# baseboard.net
KiCad netlist of a schematic drawn in EAGLE
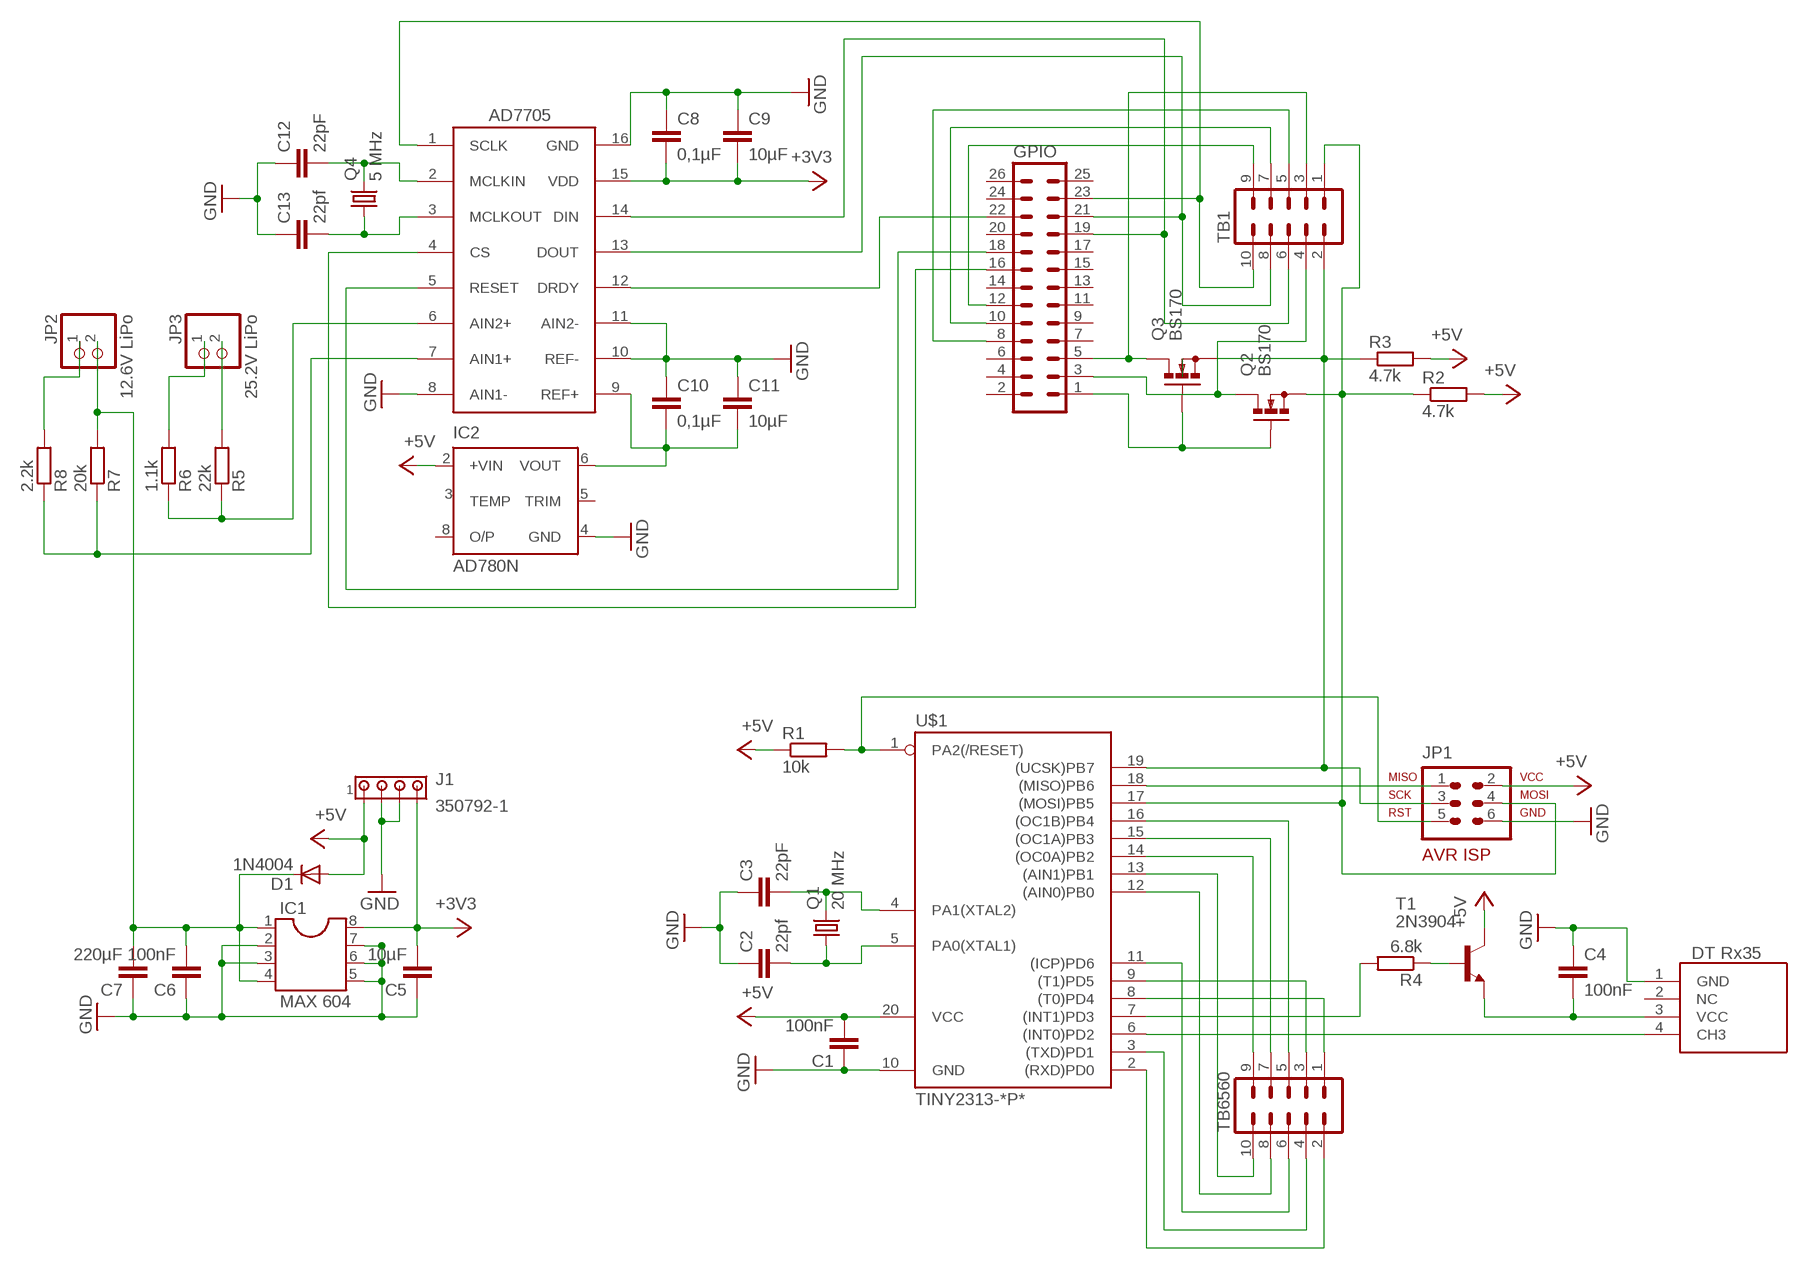
[diagram p0: schematic, sheet 1]

(export (version "E")
  (design (tool "Eeschema 10.0.6"))
  (components
    (comp (ref "C1")
      (value "100nF")
      (footprint "eagle-import:C2.5-2")
      (libsource (lib "eagle-import") (part "C2.5/2"))
    )
    (comp (ref "C2")
      (value "22pf")
      (footprint "eagle-import:C2.5-2")
      (libsource (lib "eagle-import") (part "C2.5/2"))
    )
    (comp (ref "C3")
      (value "22pF")
      (footprint "eagle-import:C2.5-2")
      (libsource (lib "eagle-import") (part "C2.5/2"))
    )
    (comp (ref "C4")
      (value "100nF")
      (footprint "eagle-import:C2.5-2")
      (libsource (lib "eagle-import") (part "C2.5/2"))
    )
    (comp (ref "C5")
      (value "10µF")
      (footprint "eagle-import:C2.5-2")
      (libsource (lib "eagle-import") (part "C2.5/2"))
    )
    (comp (ref "C6")
      (value "100nF")
      (footprint "eagle-import:C2.5-2")
      (libsource (lib "eagle-import") (part "C2.5/2"))
    )
    (comp (ref "C7")
      (value "220µF")
      (footprint "eagle-import:C2.5-2")
      (libsource (lib "eagle-import") (part "C2.5/2"))
    )
    (comp (ref "C8")
      (value "0,1µF")
      (footprint "eagle-import:C2.5-2")
      (libsource (lib "eagle-import") (part "C2.5/2"))
    )
    (comp (ref "C9")
      (value "10µF")
      (footprint "eagle-import:C2.5-2")
      (libsource (lib "eagle-import") (part "C2.5/2"))
    )
    (comp (ref "C10")
      (value "0,1µF")
      (footprint "eagle-import:C2.5-2")
      (libsource (lib "eagle-import") (part "C2.5/2"))
    )
    (comp (ref "C11")
      (value "10µF")
      (footprint "eagle-import:C2.5-2")
      (libsource (lib "eagle-import") (part "C2.5/2"))
    )
    (comp (ref "C12")
      (value "22pF")
      (footprint "eagle-import:C2.5-2")
      (libsource (lib "eagle-import") (part "C2.5/2"))
    )
    (comp (ref "C13")
      (value "22pf")
      (footprint "eagle-import:C2.5-2")
      (libsource (lib "eagle-import") (part "C2.5/2"))
    )
    (comp (ref "D1")
      (value "1N4004")
      (footprint "eagle-import:DO41-10")
      (libsource (lib "eagle-import") (part "1N4004"))
    )
    (comp (ref "GPIO")
      (value "ML26")
      (footprint "eagle-import:ML26")
      (libsource (lib "eagle-import") (part "ML26"))
    )
    (comp (ref "IC1")
      (value "MAX 604")
      (footprint "eagle-import:DIL08")
      (libsource (lib "eagle-import") (part "DIL8"))
    )
    (comp (ref "IC2")
      (value "AD780N")
      (footprint "eagle-import:DIL08")
      (fields (field (name "MF") "ALTERA CORPORATION") (field (name "MPN") "AD780ANZ"))
      (libsource (lib "eagle-import") (part "AD780N"))
    )
    (comp (ref "J1")
      (value "350792-1")
      (footprint "eagle-import:350792-1")
      (libsource (lib "eagle-import") (part "350792-1"))
    )
    (comp (ref "JP1")
      (value "AVR-ISP-6VERT")
      (footprint "eagle-import:AVR-ISP-6")
      (libsource (lib "eagle-import") (part "AVR-ISP-6VERT"))
    )
    (comp (ref "JP2")
      (value "12.6V LiPo")
      (footprint "eagle-import:1X02")
      (libsource (lib "eagle-import") (part "PINHD-1X2"))
    )
    (comp (ref "JP3")
      (value "25.2V LiPo")
      (footprint "eagle-import:1X02")
      (libsource (lib "eagle-import") (part "PINHD-1X2"))
    )
    (comp (ref "Q1")
      (value "20 MHz")
      (footprint "eagle-import:HC49_S")
      (libsource (lib "eagle-import") (part "CRYSTALHC49S"))
    )
    (comp (ref "Q2")
      (value "BS170")
      (footprint "eagle-import:SOT54E")
      (libsource (lib "eagle-import") (part "BS170"))
    )
    (comp (ref "Q3")
      (value "BS170")
      (footprint "eagle-import:SOT54E")
      (libsource (lib "eagle-import") (part "BS170"))
    )
    (comp (ref "Q4")
      (value "5 MHz")
      (footprint "eagle-import:HC49_S")
      (libsource (lib "eagle-import") (part "CRYSTALHC49S"))
    )
    (comp (ref "R1")
      (value "10k")
      (footprint "eagle-import:0207_2V")
      (libsource (lib "eagle-import") (part "R-EU_0207/2V"))
    )
    (comp (ref "R2")
      (value "4.7k")
      (footprint "eagle-import:0207_2V")
      (libsource (lib "eagle-import") (part "R-EU_0207/2V"))
    )
    (comp (ref "R3")
      (value "4.7k")
      (footprint "eagle-import:0207_2V")
      (libsource (lib "eagle-import") (part "R-EU_0207/2V"))
    )
    (comp (ref "R4")
      (value "6.8k")
      (footprint "eagle-import:0207_12")
      (libsource (lib "eagle-import") (part "R-EU_0207/12"))
    )
    (comp (ref "R5")
      (value "22k")
      (footprint "eagle-import:0207_2V")
      (libsource (lib "eagle-import") (part "R-EU_0207/2V"))
    )
    (comp (ref "R6")
      (value "1.1k")
      (footprint "eagle-import:0207_2V")
      (libsource (lib "eagle-import") (part "R-EU_0207/2V"))
    )
    (comp (ref "R7")
      (value "20k")
      (footprint "eagle-import:0207_2V")
      (libsource (lib "eagle-import") (part "R-EU_0207/2V"))
    )
    (comp (ref "R8")
      (value "2.2k")
      (footprint "eagle-import:0207_2V")
      (libsource (lib "eagle-import") (part "R-EU_0207/2V"))
    )
    (comp (ref "T1")
      (value "2N3904")
      (footprint "eagle-import:TO92")
      (libsource (lib "eagle-import") (part "2N3904"))
    )
    (comp (ref "TB1")
      (value "ML10")
      (footprint "eagle-import:ML10")
      (libsource (lib "eagle-import") (part "ML10"))
    )
    (comp (ref "TB6560")
      (value "ML10")
      (footprint "eagle-import:ML10")
      (libsource (lib "eagle-import") (part "ML10"))
    )
    (comp (ref "U$1")
      (value "TINY2313-*P*")
      (footprint "eagle-import:DIL20")
      (libsource (lib "eagle-import") (part "TINY2313-P"))
    )
    (comp (ref "U$2")
      (value "DTRX35")
      (footprint "eagle-import:DTRX35")
      (libsource (lib "eagle-import") (part "DTRX35"))
    )
    (comp (ref "U$3")
      (value "AD7705")
      (footprint "eagle-import:AD7705BNC")
      (libsource (lib "eagle-import") (part "AD7705"))
    )
  )
  (nets
    (net (code "1") (name "+3V3") (class "Default")
      (node (ref "C5") (pin "2") (pinfunction "2_2") (pintype "passive"))
      (node (ref "C8") (pin "2") (pinfunction "2_2") (pintype "passive"))
      (node (ref "C9") (pin "2") (pinfunction "2_2") (pintype "passive"))
      (node (ref "IC1") (pin "8") (pinfunction "8_8") (pintype "passive"))
      (node (ref "J1") (pin "4") (pinfunction "4_4") (pintype "passive"))
      (node (ref "U$3") (pin "15") (pinfunction "VDD_15") (pintype "power_in"))
    )
    (net (code "2") (name "+5V") (class "Default")
      (node (ref "C1") (pin "2") (pinfunction "2_2") (pintype "passive"))
      (node (ref "D1") (pin "A") (pinfunction "A_A") (pintype "passive"))
      (node (ref "IC2") (pin "2") (pinfunction "+VIN_2") (pintype "input"))
      (node (ref "J1") (pin "1") (pinfunction "1_1") (pintype "passive"))
      (node (ref "JP1") (pin "2") (pinfunction "2_2") (pintype "passive"))
      (node (ref "R1") (pin "1") (pinfunction "1_1") (pintype "passive"))
      (node (ref "R2") (pin "2") (pinfunction "2_2") (pintype "passive"))
      (node (ref "R3") (pin "2") (pinfunction "2_2") (pintype "passive"))
      (node (ref "T1") (pin "1") (pinfunction "C_1") (pintype "passive"))
      (node (ref "U$1") (pin "20") (pinfunction "VCC_20") (pintype "power_in"))
    )
    (net (code "3") (name "GND") (class "Default")
      (node (ref "C1") (pin "1") (pinfunction "1_1") (pintype "passive"))
      (node (ref "C10") (pin "1") (pinfunction "1_1") (pintype "passive"))
      (node (ref "C11") (pin "1") (pinfunction "1_1") (pintype "passive"))
      (node (ref "C12") (pin "1") (pinfunction "1_1") (pintype "passive"))
      (node (ref "C13") (pin "1") (pinfunction "1_1") (pintype "passive"))
      (node (ref "C2") (pin "1") (pinfunction "1_1") (pintype "passive"))
      (node (ref "C3") (pin "1") (pinfunction "1_1") (pintype "passive"))
      (node (ref "C4") (pin "1") (pinfunction "1_1") (pintype "passive"))
      (node (ref "C5") (pin "1") (pinfunction "1_1") (pintype "passive"))
      (node (ref "C6") (pin "1") (pinfunction "1_1") (pintype "passive"))
      (node (ref "C7") (pin "1") (pinfunction "1_1") (pintype "passive"))
      (node (ref "C8") (pin "1") (pinfunction "1_1") (pintype "passive"))
      (node (ref "C9") (pin "1") (pinfunction "1_1") (pintype "passive"))
      (node (ref "IC1") (pin "2") (pinfunction "2_2") (pintype "passive"))
      (node (ref "IC1") (pin "3") (pinfunction "3_3") (pintype "passive"))
      (node (ref "IC1") (pin "5") (pinfunction "5_5") (pintype "passive"))
      (node (ref "IC1") (pin "6") (pinfunction "6_6") (pintype "passive"))
      (node (ref "IC1") (pin "7") (pinfunction "7_7") (pintype "passive"))
      (node (ref "IC2") (pin "4") (pinfunction "GND_4") (pintype "power_in"))
      (node (ref "J1") (pin "2") (pinfunction "2_2") (pintype "passive"))
      (node (ref "J1") (pin "3") (pinfunction "3_3") (pintype "passive"))
      (node (ref "JP1") (pin "6") (pinfunction "6_6") (pintype "passive"))
      (node (ref "U$1") (pin "10") (pinfunction "GND_10") (pintype "power_in"))
      (node (ref "U$2") (pin "1") (pinfunction "GND_1") (pintype "input"))
      (node (ref "U$3") (pin "10") (pinfunction "REF-_10") (pintype "input"))
      (node (ref "U$3") (pin "11") (pinfunction "AIN2-_11") (pintype "input"))
      (node (ref "U$3") (pin "16") (pinfunction "GND_16") (pintype "input"))
      (node (ref "U$3") (pin "8") (pinfunction "AIN1-_8") (pintype "input"))
    )
    (net (code "4") (name "Net-(C6-Pad2)") (class "Default")
      (node (ref "C6") (pin "2") (pinfunction "2_2") (pintype "passive"))
      (node (ref "C7") (pin "2") (pinfunction "2_2") (pintype "passive"))
      (node (ref "D1") (pin "C") (pinfunction "C_C") (pintype "passive"))
      (node (ref "IC1") (pin "1") (pinfunction "1_1") (pintype "passive"))
      (node (ref "IC1") (pin "4") (pinfunction "4_4") (pintype "passive"))
      (node (ref "JP2") (pin "2") (pinfunction "2_2") (pintype "passive"))
      (node (ref "R7") (pin "2") (pinfunction "2_2") (pintype "passive"))
    )
    (net (code "5") (name "Net-(GPIO-Pad1)") (class "Default")
      (node (ref "GPIO") (pin "1") (pinfunction "1_1") (pintype "passive"))
      (node (ref "Q2") (pin "G") (pinfunction "G_G") (pintype "passive"))
      (node (ref "Q3") (pin "G") (pinfunction "G_G") (pintype "passive"))
    )
    (net (code "6") (name "Net-(GPIO-Pad3)") (class "Default")
      (node (ref "GPIO") (pin "3") (pinfunction "3_3") (pintype "passive"))
      (node (ref "Q2") (pin "D") (pinfunction "D_D") (pintype "passive"))
      (node (ref "TB1") (pin "4") (pinfunction "4_4") (pintype "passive"))
    )
    (net (code "7") (name "Net-(GPIO-Pad5)") (class "Default")
      (node (ref "GPIO") (pin "5") (pinfunction "5_5") (pintype "passive"))
      (node (ref "Q3") (pin "D") (pinfunction "D_D") (pintype "passive"))
      (node (ref "TB1") (pin "3") (pinfunction "3_3") (pintype "passive"))
    )
    (net (code "8") (name "Net-(GPIO-Pad8)") (class "Default")
      (node (ref "GPIO") (pin "8") (pinfunction "8_8") (pintype "passive"))
      (node (ref "TB1") (pin "5") (pinfunction "5_5") (pintype "passive"))
    )
    (net (code "9") (name "Net-(GPIO-Pad10)") (class "Default")
      (node (ref "GPIO") (pin "10") (pinfunction "10_10") (pintype "passive"))
      (node (ref "TB1") (pin "7") (pinfunction "7_7") (pintype "passive"))
    )
    (net (code "10") (name "Net-(GPIO-Pad12)") (class "Default")
      (node (ref "GPIO") (pin "12") (pinfunction "12_12") (pintype "passive"))
      (node (ref "TB1") (pin "9") (pinfunction "9_9") (pintype "passive"))
    )
    (net (code "11") (name "Net-(IC2-VOUT)") (class "Default")
      (node (ref "C10") (pin "2") (pinfunction "2_2") (pintype "passive"))
      (node (ref "C11") (pin "2") (pinfunction "2_2") (pintype "passive"))
      (node (ref "IC2") (pin "6") (pinfunction "VOUT_6") (pintype "input"))
      (node (ref "U$3") (pin "9") (pinfunction "REF+_9") (pintype "input"))
    )
    (net (code "12") (name "Net-(JP2-Pad1)") (class "Default")
      (node (ref "JP2") (pin "1") (pinfunction "1_1") (pintype "passive"))
      (node (ref "R8") (pin "2") (pinfunction "2_2") (pintype "passive"))
    )
    (net (code "13") (name "Net-(JP3-Pad1)") (class "Default")
      (node (ref "JP3") (pin "1") (pinfunction "1_1") (pintype "passive"))
      (node (ref "R6") (pin "2") (pinfunction "2_2") (pintype "passive"))
    )
    (net (code "14") (name "Net-(JP3-Pad2)") (class "Default")
      (node (ref "JP3") (pin "2") (pinfunction "2_2") (pintype "passive"))
      (node (ref "R5") (pin "2") (pinfunction "2_2") (pintype "passive"))
    )
    (net (code "15") (name "Net-(T1-B)") (class "Default")
      (node (ref "R4") (pin "1") (pinfunction "1_1") (pintype "passive"))
      (node (ref "T1") (pin "2") (pinfunction "B_2") (pintype "passive"))
    )
    (net (code "16") (name "Net-(T1-E)") (class "Default")
      (node (ref "C4") (pin "2") (pinfunction "2_2") (pintype "passive"))
      (node (ref "T1") (pin "3") (pinfunction "E_3") (pintype "passive"))
      (node (ref "U$2") (pin "3") (pinfunction "VCC_3") (pintype "power_in"))
    )
    (net (code "17") (name "Net-(U$1-(AIN0)PB0)") (class "Default")
      (node (ref "TB6560") (pin "8") (pinfunction "8_8") (pintype "passive"))
      (node (ref "U$1") (pin "12") (pinfunction "(AIN0)PB0_12") (pintype "bidirectional"))
    )
    (net (code "18") (name "Net-(U$1-(AIN1)PB1)") (class "Default")
      (node (ref "TB6560") (pin "10") (pinfunction "10_10") (pintype "passive"))
      (node (ref "U$1") (pin "13") (pinfunction "(AIN1)PB1_13") (pintype "bidirectional"))
    )
    (net (code "19") (name "Net-(U$1-(ICP)PD6)") (class "Default")
      (node (ref "TB6560") (pin "6") (pinfunction "6_6") (pintype "passive"))
      (node (ref "U$1") (pin "11") (pinfunction "(ICP)PD6_11") (pintype "bidirectional"))
    )
    (net (code "20") (name "Net-(U$1-(INT0)PD2)") (class "Default")
      (node (ref "U$1") (pin "6") (pinfunction "(INT0)PD2_6") (pintype "bidirectional"))
      (node (ref "U$2") (pin "4") (pinfunction "CH3_4") (pintype "output"))
    )
    (net (code "21") (name "Net-(U$1-(INT1)PD3)") (class "Default")
      (node (ref "R4") (pin "2") (pinfunction "2_2") (pintype "passive"))
      (node (ref "U$1") (pin "7") (pinfunction "(INT1)PD3_7") (pintype "bidirectional"))
    )
    (net (code "22") (name "Net-(U$1-(MISO)PB6)") (class "Default")
      (node (ref "JP1") (pin "1") (pinfunction "1_1") (pintype "passive"))
      (node (ref "U$1") (pin "18") (pinfunction "(MISO)PB6_18") (pintype "bidirectional"))
    )
    (net (code "23") (name "Net-(U$1-(MOSI)PB5)") (class "Default")
      (node (ref "JP1") (pin "4") (pinfunction "4_4") (pintype "passive"))
      (node (ref "Q2") (pin "S") (pinfunction "S_S") (pintype "passive"))
      (node (ref "R2") (pin "1") (pinfunction "1_1") (pintype "passive"))
      (node (ref "TB1") (pin "1") (pinfunction "1_1") (pintype "passive"))
      (node (ref "U$1") (pin "17") (pinfunction "(MOSI)PB5_17") (pintype "bidirectional"))
    )
    (net (code "24") (name "Net-(U$1-(OC0A)PB2)") (class "Default")
      (node (ref "TB6560") (pin "9") (pinfunction "9_9") (pintype "passive"))
      (node (ref "U$1") (pin "14") (pinfunction "(OC0A)PB2_14") (pintype "bidirectional"))
    )
    (net (code "25") (name "Net-(U$1-(OC1A)PB3)") (class "Default")
      (node (ref "TB6560") (pin "7") (pinfunction "7_7") (pintype "passive"))
      (node (ref "U$1") (pin "15") (pinfunction "(OC1A)PB3_15") (pintype "bidirectional"))
    )
    (net (code "26") (name "Net-(U$1-(OC1B)PB4)") (class "Default")
      (node (ref "TB6560") (pin "5") (pinfunction "5_5") (pintype "passive"))
      (node (ref "U$1") (pin "16") (pinfunction "(OC1B)PB4_16") (pintype "bidirectional"))
    )
    (net (code "27") (name "Net-(U$1-(RXD)PD0)") (class "Default")
      (node (ref "TB6560") (pin "2") (pinfunction "2_2") (pintype "passive"))
      (node (ref "U$1") (pin "2") (pinfunction "(RXD)PD0_2") (pintype "bidirectional"))
    )
    (net (code "28") (name "Net-(U$1-(T0)PD4)") (class "Default")
      (node (ref "TB6560") (pin "1") (pinfunction "1_1") (pintype "passive"))
      (node (ref "U$1") (pin "8") (pinfunction "(T0)PD4_8") (pintype "bidirectional"))
    )
    (net (code "29") (name "Net-(U$1-(T1)PD5)") (class "Default")
      (node (ref "TB6560") (pin "3") (pinfunction "3_3") (pintype "passive"))
      (node (ref "U$1") (pin "9") (pinfunction "(T1)PD5_9") (pintype "bidirectional"))
    )
    (net (code "30") (name "Net-(U$1-(TXD)PD1)") (class "Default")
      (node (ref "TB6560") (pin "4") (pinfunction "4_4") (pintype "passive"))
      (node (ref "U$1") (pin "3") (pinfunction "(TXD)PD1_3") (pintype "bidirectional"))
    )
    (net (code "31") (name "Net-(U$1-(UCSK)PB7)") (class "Default")
      (node (ref "JP1") (pin "3") (pinfunction "3_3") (pintype "passive"))
      (node (ref "Q3") (pin "S") (pinfunction "S_S") (pintype "passive"))
      (node (ref "R3") (pin "1") (pinfunction "1_1") (pintype "passive"))
      (node (ref "TB1") (pin "2") (pinfunction "2_2") (pintype "passive"))
      (node (ref "U$1") (pin "19") (pinfunction "(UCSK)PB7_19") (pintype "bidirectional"))
    )
    (net (code "32") (name "Net-(U$1-PA0(XTAL1))") (class "Default")
      (node (ref "C2") (pin "2") (pinfunction "2_2") (pintype "passive"))
      (node (ref "Q1") (pin "1") (pinfunction "1_1") (pintype "passive"))
      (node (ref "U$1") (pin "5") (pinfunction "PA0(XTAL1)_5") (pintype "bidirectional"))
    )
    (net (code "33") (name "Net-(U$1-PA1(XTAL2))") (class "Default")
      (node (ref "C3") (pin "2") (pinfunction "2_2") (pintype "passive"))
      (node (ref "Q1") (pin "2") (pinfunction "2_2") (pintype "passive"))
      (node (ref "U$1") (pin "4") (pinfunction "PA1(XTAL2)_4") (pintype "bidirectional"))
    )
    (net (code "34") (name "Net-(U$1-PA2({slash}RESET))") (class "Default")
      (node (ref "JP1") (pin "5") (pinfunction "5_5") (pintype "passive"))
      (node (ref "R1") (pin "2") (pinfunction "2_2") (pintype "passive"))
      (node (ref "U$1") (pin "1") (pinfunction "PA2(/RESET)_1") (pintype "input"))
    )
    (net (code "35") (name "Net-(U$3-AIN1+)") (class "Default")
      (node (ref "R7") (pin "1") (pinfunction "1_1") (pintype "passive"))
      (node (ref "R8") (pin "1") (pinfunction "1_1") (pintype "passive"))
      (node (ref "U$3") (pin "7") (pinfunction "AIN1+_7") (pintype "input"))
    )
    (net (code "36") (name "Net-(U$3-AIN2+)") (class "Default")
      (node (ref "R5") (pin "1") (pinfunction "1_1") (pintype "passive"))
      (node (ref "R6") (pin "1") (pinfunction "1_1") (pintype "passive"))
      (node (ref "U$3") (pin "6") (pinfunction "AIN2+_6") (pintype "input"))
    )
    (net (code "37") (name "Net-(U$3-CS)") (class "Default")
      (node (ref "GPIO") (pin "16") (pinfunction "16_16") (pintype "passive"))
      (node (ref "U$3") (pin "4") (pinfunction "CS_4") (pintype "input"))
    )
    (net (code "38") (name "Net-(U$3-DIN)") (class "Default")
      (node (ref "GPIO") (pin "19") (pinfunction "19_19") (pintype "passive"))
      (node (ref "TB1") (pin "6") (pinfunction "6_6") (pintype "passive"))
      (node (ref "U$3") (pin "14") (pinfunction "DIN_14") (pintype "bidirectional"))
    )
    (net (code "39") (name "Net-(U$3-DOUT)") (class "Default")
      (node (ref "GPIO") (pin "21") (pinfunction "21_21") (pintype "passive"))
      (node (ref "TB1") (pin "8") (pinfunction "8_8") (pintype "passive"))
      (node (ref "U$3") (pin "13") (pinfunction "DOUT_13") (pintype "bidirectional"))
    )
    (net (code "40") (name "Net-(U$3-DRDY)") (class "Default")
      (node (ref "GPIO") (pin "22") (pinfunction "22_22") (pintype "passive"))
      (node (ref "U$3") (pin "12") (pinfunction "DRDY_12") (pintype "bidirectional"))
    )
    (net (code "41") (name "Net-(U$3-MCLKIN)") (class "Default")
      (node (ref "C12") (pin "2") (pinfunction "2_2") (pintype "passive"))
      (node (ref "Q4") (pin "2") (pinfunction "2_2") (pintype "passive"))
      (node (ref "U$3") (pin "2") (pinfunction "MCLKIN_2") (pintype "input"))
    )
    (net (code "42") (name "Net-(U$3-MCLKOUT)") (class "Default")
      (node (ref "C13") (pin "2") (pinfunction "2_2") (pintype "passive"))
      (node (ref "Q4") (pin "1") (pinfunction "1_1") (pintype "passive"))
      (node (ref "U$3") (pin "3") (pinfunction "MCLKOUT_3") (pintype "output"))
    )
    (net (code "43") (name "Net-(U$3-RESET)") (class "Default")
      (node (ref "GPIO") (pin "18") (pinfunction "18_18") (pintype "passive"))
      (node (ref "U$3") (pin "5") (pinfunction "RESET_5") (pintype "input"))
    )
    (net (code "44") (name "Net-(U$3-SCLK)") (class "Default")
      (node (ref "GPIO") (pin "23") (pinfunction "23_23") (pintype "passive"))
      (node (ref "TB1") (pin "10") (pinfunction "10_10") (pintype "passive"))
      (node (ref "U$3") (pin "1") (pinfunction "SCLK_1") (pintype "bidirectional"))
    )
    (net (code "45") (name "unconnected-(GPIO-Pad2)") (class "Default")
      (node (ref "GPIO") (pin "2") (pinfunction "2_2") (pintype "passive"))
    )
    (net (code "46") (name "unconnected-(GPIO-Pad4)") (class "Default")
      (node (ref "GPIO") (pin "4") (pinfunction "4_4") (pintype "passive"))
    )
    (net (code "47") (name "unconnected-(GPIO-Pad6)") (class "Default")
      (node (ref "GPIO") (pin "6") (pinfunction "6_6") (pintype "passive"))
    )
    (net (code "48") (name "unconnected-(GPIO-Pad7)") (class "Default")
      (node (ref "GPIO") (pin "7") (pinfunction "7_7") (pintype "passive"))
    )
    (net (code "49") (name "unconnected-(GPIO-Pad9)") (class "Default")
      (node (ref "GPIO") (pin "9") (pinfunction "9_9") (pintype "passive"))
    )
    (net (code "50") (name "unconnected-(GPIO-Pad11)") (class "Default")
      (node (ref "GPIO") (pin "11") (pinfunction "11_11") (pintype "passive"))
    )
    (net (code "51") (name "unconnected-(GPIO-Pad13)") (class "Default")
      (node (ref "GPIO") (pin "13") (pinfunction "13_13") (pintype "passive"))
    )
    (net (code "52") (name "unconnected-(GPIO-Pad14)") (class "Default")
      (node (ref "GPIO") (pin "14") (pinfunction "14_14") (pintype "passive"))
    )
    (net (code "53") (name "unconnected-(GPIO-Pad15)") (class "Default")
      (node (ref "GPIO") (pin "15") (pinfunction "15_15") (pintype "passive"))
    )
    (net (code "54") (name "unconnected-(GPIO-Pad17)") (class "Default")
      (node (ref "GPIO") (pin "17") (pinfunction "17_17") (pintype "passive"))
    )
    (net (code "55") (name "unconnected-(GPIO-Pad20)") (class "Default")
      (node (ref "GPIO") (pin "20") (pinfunction "20_20") (pintype "passive"))
    )
    (net (code "56") (name "unconnected-(GPIO-Pad24)") (class "Default")
      (node (ref "GPIO") (pin "24") (pinfunction "24_24") (pintype "passive"))
    )
    (net (code "57") (name "unconnected-(GPIO-Pad25)") (class "Default")
      (node (ref "GPIO") (pin "25") (pinfunction "25_25") (pintype "passive"))
    )
    (net (code "58") (name "unconnected-(GPIO-Pad26)") (class "Default")
      (node (ref "GPIO") (pin "26") (pinfunction "26_26") (pintype "passive"))
    )
    (net (code "59") (name "unconnected-(IC2-O{slash}P-Pad8)") (class "Default")
      (node (ref "IC2") (pin "8") (pinfunction "O/P_8") (pintype "passive"))
    )
    (net (code "60") (name "unconnected-(IC2-TEMP-Pad3)") (class "Default")
      (node (ref "IC2") (pin "3") (pinfunction "TEMP_3") (pintype "input"))
    )
    (net (code "61") (name "unconnected-(IC2-TRIM-Pad5)") (class "Default")
      (node (ref "IC2") (pin "5") (pinfunction "TRIM_5") (pintype "input"))
    )
    (net (code "62") (name "unconnected-(U$2-NC-Pad2)") (class "Default")
      (node (ref "U$2") (pin "2") (pinfunction "NC_2") (pintype "no_connect"))
    )
  )
)
